# Car_Power_Supply.net
KiCad netlist of a schematic drawn in Altium Designer
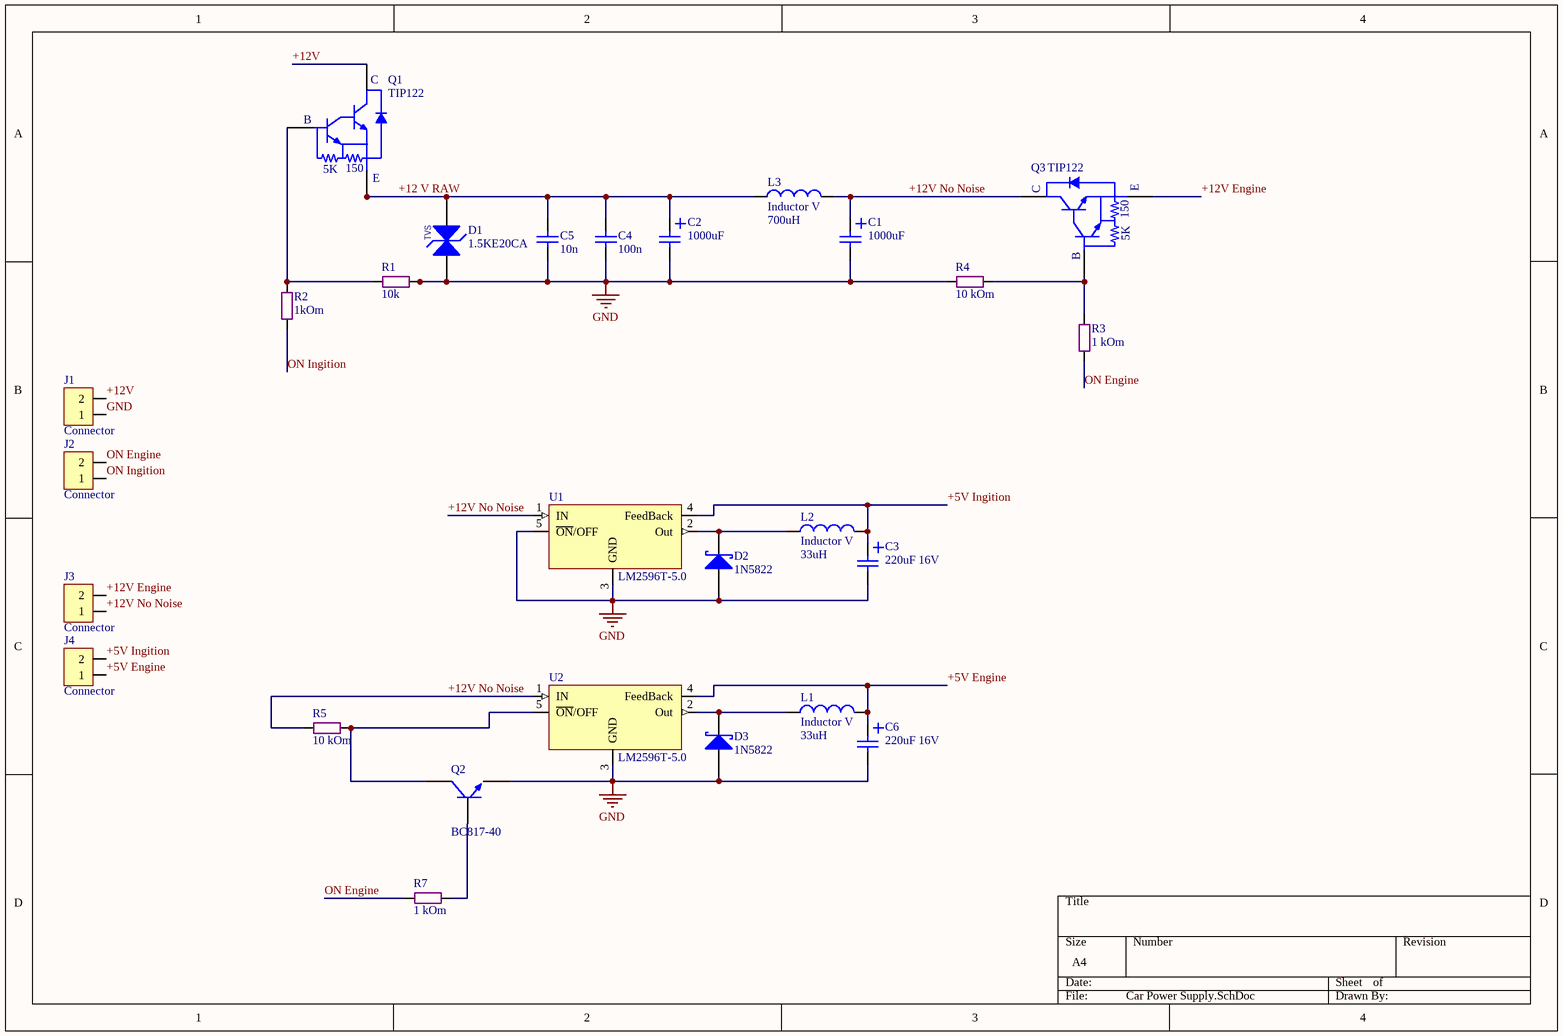
[diagram p0: Car Power Supply.SchDoc]

(export (version "E")
  (design (tool "Eeschema 10.0.6"))
  (components
    (comp (ref "C1")
      (value "1000uF")
      (footprint "Capacitor:Cap E p5.08mm D10.2mm (3p)")
      (description "Capacitor")
      (libsource (lib "Capacitor") (part "Cap E 1000mF x 25V"))
    )
    (comp (ref "C2")
      (value "1000uF")
      (footprint "Capacitor:Cap E p5.08mm D10.2mm (3p)")
      (description "Capacitor")
      (libsource (lib "Capacitor") (part "Cap E 1000mF x 25V"))
    )
    (comp (ref "C3")
      (value "220uF 16V")
      (footprint "Capacitor:Cap E p2mm D6.5xH11")
      (description "Capacitor")
      (libsource (lib "Capacitor") (part "Cap E 220mF x 16V"))
    )
    (comp (ref "C4")
      (value "100n")
      (footprint "Capacitor:Cap P5.08MM (3p) disk2")
      (description "Capacitor")
      (libsource (lib "Capacitor") (part "Cap Ceramic"))
    )
    (comp (ref "C5")
      (value "10n")
      (footprint "Capacitor:Cap P5.08MM (3p) disk2")
      (description "Capacitor")
      (libsource (lib "Capacitor") (part "Cap Ceramic"))
    )
    (comp (ref "C6")
      (value "220uF 16V")
      (footprint "Capacitor:Cap E p2mm D6.5xH11")
      (description "Capacitor")
      (libsource (lib "Capacitor") (part "Cap E 220mF x 16V"))
    )
    (comp (ref "D1")
      (value "1.5KE20CA")
      (footprint "Diodes:TVS diode DO-201 V")
      (description "1500W Transil (TVS Diode)")
      (libsource (lib "Diodes") (part "TVS 1.5KE20CA"))
    )
    (comp (ref "D2")
      (value "1N5822")
      (footprint "Diodes:Diode DO-201")
      (description "3 Amp Shotki  Diode")
      (libsource (lib "Diodes") (part "D Shotki 1N5822"))
    )
    (comp (ref "D3")
      (value "1N5822")
      (footprint "Diodes:Diode DO-201 V")
      (description "3 Amp Shotki  Diode")
      (libsource (lib "Diodes") (part "D Shotki 1N5822"))
    )
    (comp (ref "J1")
      (value "Connector")
      (footprint "Connector:DG301 5mm 2p")
      (description "DG301 series")
      (libsource (lib "Connector") (part "DG301-5.0-2P12"))
    )
    (comp (ref "J2")
      (value "Connector")
      (footprint "Connector:DG301 5mm 2p")
      (description "DG301 series")
      (libsource (lib "Connector") (part "DG301-5.0-2P12"))
    )
    (comp (ref "J3")
      (value "Connector")
      (footprint "Connector:DG301 5mm 2p")
      (description "DG301 series")
      (libsource (lib "Connector") (part "DG301-5.0-2P12"))
    )
    (comp (ref "J4")
      (value "Connector")
      (footprint "Connector:DG301 5mm 2p")
      (description "DG301 series")
      (libsource (lib "Connector") (part "DG301-5.0-2P12"))
    )
    (comp (ref "L1")
      (value "Inductor V")
      (footprint "Transformers:Toroid V D14-W6")
      (description "Inductor Vertical")
      (fields (field (name "ALTIUM_VALUE") "33uH") (field (name "PUBLISHER") "Altium Limited"))
      (libsource (lib "Transformers") (part "Inductor V"))
    )
    (comp (ref "L2")
      (value "Inductor V")
      (footprint "Transformers:Toroid V D14-W6")
      (description "Inductor Vertical")
      (fields (field (name "ALTIUM_VALUE") "33uH") (field (name "PUBLISHER") "Altium Limited"))
      (libsource (lib "Transformers") (part "Inductor V"))
    )
    (comp (ref "L3")
      (value "Inductor V")
      (footprint "Transformers:Toroid V D14-W6")
      (description "Inductor Vertical")
      (fields (field (name "ALTIUM_VALUE") "700uH") (field (name "PUBLISHER") "Altium Limited"))
      (libsource (lib "Transformers") (part "Inductor V"))
    )
    (comp (ref "Q1")
      (value "TIP122")
      (footprint "GeneralCases:TO220-2")
      (description "NPN Darlington 5A, 65W, 100V, h>1000")
      (libsource (lib "Transistor") (part "TIP122"))
    )
    (comp (ref "Q2")
      (value "BC817-40")
      (footprint "GeneralCases:SOT-23")
      (description "NPN 45 V, 500 mA NPN general-purpose transistor")
      (libsource (lib "Transistor") (part "BC817-40"))
    )
    (comp (ref "Q3")
      (value "TIP122")
      (footprint "GeneralCases:TO220-2")
      (description "NPN Darlington 5A, 65W, 100V, h>1000")
      (libsource (lib "Transistor") (part "TIP122"))
    )
    (comp (ref "R1")
      (value "10k")
      (footprint "SMD 0805 (2012)")
      (libsource (lib "PassiveComponents") (part "Res SMD 0805"))
    )
    (comp (ref "R2")
      (value "1kOm")
      (footprint "SMD 0805 (2012)")
      (libsource (lib "PassiveComponents") (part "Res SMD 0805"))
    )
    (comp (ref "R3")
      (value "1 kOm")
      (footprint "PassiveComponents:Res p7.62 (4p) 0.25w")
      (libsource (lib "PassiveComponents") (part "Res All Types"))
    )
    (comp (ref "R4")
      (value "10 kOm")
      (footprint "SMD 0805 (2012)")
      (libsource (lib "PassiveComponents") (part "Res SMD 0805"))
    )
    (comp (ref "R5")
      (value "10 kOm")
      (footprint "PassiveComponents:Res p7.62 (4p) 0.25w")
      (libsource (lib "PassiveComponents") (part "Res All Types"))
    )
    (comp (ref "R7")
      (value "1 kOm")
      (footprint "PassiveComponents:Res p7.62 (4p) 0.25w")
      (libsource (lib "PassiveComponents") (part "Res All Types"))
    )
    (comp (ref "U1")
      (value "LM2596T-5.0")
      (footprint "GeneralCases:TO220-5 Vertical")
      (description "Voltage Regulator")
      (fields (field (name "MANUFACTURER") "National Semiconductor"))
      (libsource (lib "PowerAdjusment") (part "LM2596T-5.0"))
    )
    (comp (ref "U2")
      (value "LM2596T-5.0")
      (footprint "GeneralCases:TO220-5 Vertical")
      (description "Voltage Regulator")
      (fields (field (name "MANUFACTURER") "National Semiconductor"))
      (libsource (lib "PowerAdjusment") (part "LM2596T-5.0"))
    )
  )
  (nets
    (net (code "1") (name "/+5V Engine") (class "Default")
      (node (ref "C6") (pin "1") (pinfunction "1_1") (pintype "passive"))
      (node (ref "J4") (pin "1") (pinfunction "1_1") (pintype "passive"))
      (node (ref "L1") (pin "2") (pinfunction "2_2") (pintype "passive"))
      (node (ref "U2") (pin "4") (pinfunction "FeedBack_4") (pintype "passive"))
    )
    (net (code "2") (name "/+5V Ingition") (class "Default")
      (node (ref "C3") (pin "1") (pinfunction "1_1") (pintype "passive"))
      (node (ref "J4") (pin "2") (pinfunction "2_2") (pintype "passive"))
      (node (ref "L2") (pin "2") (pinfunction "2_2") (pintype "passive"))
      (node (ref "U1") (pin "4") (pinfunction "FeedBack_4") (pintype "passive"))
    )
    (net (code "3") (name "/+12 V RAW") (class "Default")
      (node (ref "C2") (pin "1") (pinfunction "1_1") (pintype "passive"))
      (node (ref "C4") (pin "1") (pinfunction "1_1") (pintype "passive"))
      (node (ref "C5") (pin "1") (pinfunction "1_1") (pintype "passive"))
      (node (ref "D1") (pin "2") (pinfunction "2_2") (pintype "passive"))
      (node (ref "L3") (pin "1") (pinfunction "1_1") (pintype "passive"))
      (node (ref "Q1") (pin "3") (pinfunction "E_3") (pintype "passive"))
    )
    (net (code "4") (name "/+12V") (class "Default")
      (node (ref "J1") (pin "2") (pinfunction "2_2") (pintype "passive"))
      (node (ref "Q1") (pin "2") (pinfunction "C_2") (pintype "passive"))
    )
    (net (code "5") (name "/+12V Engine") (class "Default")
      (node (ref "J3") (pin "2") (pinfunction "2_2") (pintype "passive"))
      (node (ref "Q3") (pin "3") (pinfunction "E_3") (pintype "passive"))
    )
    (net (code "6") (name "/+12V No Noise") (class "Default")
      (node (ref "C1") (pin "1") (pinfunction "1_1") (pintype "passive"))
      (node (ref "J3") (pin "1") (pinfunction "1_1") (pintype "passive"))
      (node (ref "L3") (pin "2") (pinfunction "2_2") (pintype "passive"))
      (node (ref "Q3") (pin "2") (pinfunction "C_2") (pintype "passive"))
      (node (ref "R5") (pin "1") (pinfunction "1_1") (pintype "passive"))
      (node (ref "U1") (pin "1") (pinfunction "IN_1") (pintype "input"))
      (node (ref "U2") (pin "1") (pinfunction "IN_1") (pintype "input"))
    )
    (net (code "7") (name "/ON Engine") (class "Default")
      (node (ref "J2") (pin "2") (pinfunction "2_2") (pintype "passive"))
      (node (ref "R3") (pin "1") (pinfunction "1_1") (pintype "passive"))
      (node (ref "R7") (pin "1") (pinfunction "1_1") (pintype "passive"))
    )
    (net (code "8") (name "/ON Ingition") (class "Default")
      (node (ref "J2") (pin "1") (pinfunction "1_1") (pintype "passive"))
      (node (ref "R2") (pin "1") (pinfunction "1_1") (pintype "passive"))
    )
    (net (code "9") (name "GND") (class "Default")
      (node (ref "C1") (pin "2") (pinfunction "2_2") (pintype "passive"))
      (node (ref "C2") (pin "2") (pinfunction "2_2") (pintype "passive"))
      (node (ref "C3") (pin "2") (pinfunction "2_2") (pintype "passive"))
      (node (ref "C4") (pin "2") (pinfunction "2_2") (pintype "passive"))
      (node (ref "C5") (pin "2") (pinfunction "2_2") (pintype "passive"))
      (node (ref "C6") (pin "2") (pinfunction "2_2") (pintype "passive"))
      (node (ref "D1") (pin "1") (pinfunction "1_1") (pintype "passive"))
      (node (ref "D2") (pin "A") (pinfunction "A_A") (pintype "passive"))
      (node (ref "D3") (pin "A") (pinfunction "A_A") (pintype "passive"))
      (node (ref "J1") (pin "1") (pinfunction "1_1") (pintype "passive"))
      (node (ref "Q2") (pin "2") (pinfunction "E_2") (pintype "passive"))
      (node (ref "R1") (pin "2") (pinfunction "2_2") (pintype "passive"))
      (node (ref "R4") (pin "2") (pinfunction "2_2") (pintype "passive"))
      (node (ref "U1") (pin "3") (pinfunction "GND_3") (pintype "passive"))
      (node (ref "U1") (pin "5") (pinfunction "~{ON}/OFF_5") (pintype "passive"))
      (node (ref "U2") (pin "3") (pinfunction "GND_3") (pintype "passive"))
    )
    (net (code "10") (name "Net-(Q1-B)") (class "Default")
      (node (ref "Q1") (pin "1") (pinfunction "B_1") (pintype "passive"))
      (node (ref "R1") (pin "1") (pinfunction "1_1") (pintype "passive"))
      (node (ref "R2") (pin "2") (pinfunction "2_2") (pintype "passive"))
    )
    (net (code "11") (name "Net-(Q2-B)") (class "Default")
      (node (ref "Q2") (pin "1") (pinfunction "B_1") (pintype "passive"))
      (node (ref "R7") (pin "2") (pinfunction "2_2") (pintype "passive"))
    )
    (net (code "12") (name "Net-(Q2-C)") (class "Default")
      (node (ref "Q2") (pin "3") (pinfunction "C_3") (pintype "passive"))
      (node (ref "R5") (pin "2") (pinfunction "2_2") (pintype "passive"))
      (node (ref "U2") (pin "5") (pinfunction "~{ON}/OFF_5") (pintype "passive"))
    )
    (net (code "13") (name "Net-(Q3-B)") (class "Default")
      (node (ref "Q3") (pin "1") (pinfunction "B_1") (pintype "passive"))
      (node (ref "R3") (pin "2") (pinfunction "2_2") (pintype "passive"))
      (node (ref "R4") (pin "1") (pinfunction "1_1") (pintype "passive"))
    )
    (net (code "14") (name "Net-(U1-Out)") (class "Default")
      (node (ref "D2") (pin "K") (pinfunction "K_K") (pintype "passive"))
      (node (ref "L2") (pin "1") (pinfunction "1_1") (pintype "passive"))
      (node (ref "U1") (pin "2") (pinfunction "Out_2") (pintype "output"))
    )
    (net (code "15") (name "Net-(U2-Out)") (class "Default")
      (node (ref "D3") (pin "K") (pinfunction "K_K") (pintype "passive"))
      (node (ref "L1") (pin "1") (pinfunction "1_1") (pintype "passive"))
      (node (ref "U2") (pin "2") (pinfunction "Out_2") (pintype "output"))
    )
  )
)
